# LQFP.net
KiCad netlist of a schematic drawn in Altium Designer
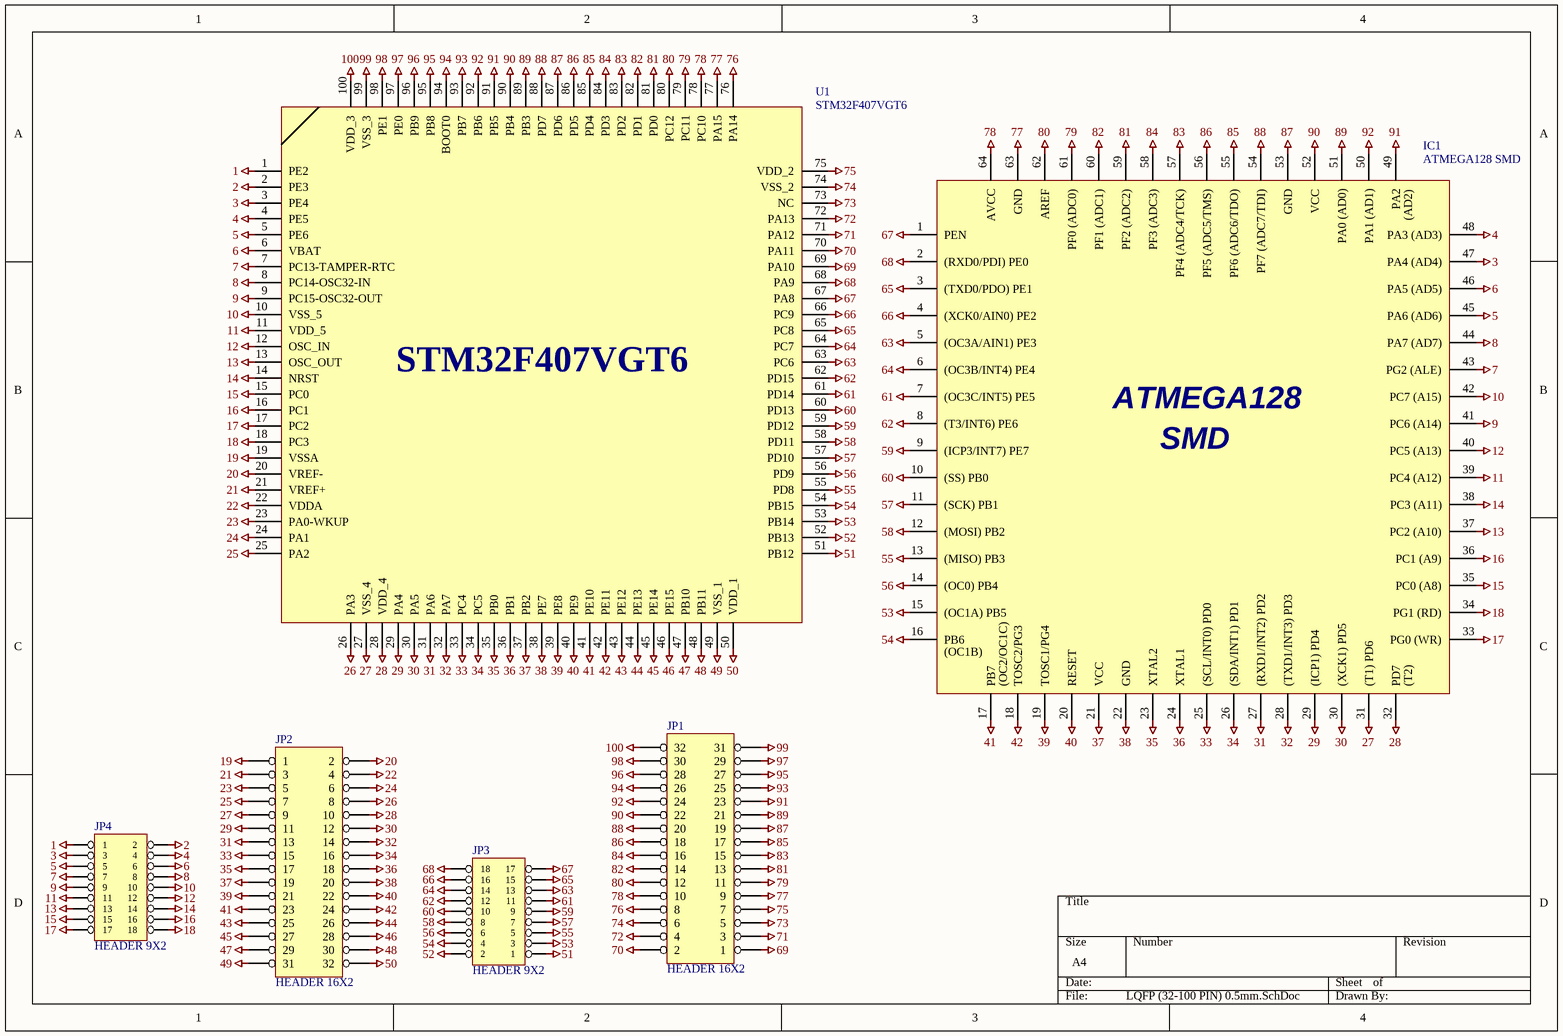
[diagram p0: LQFP (32-100 PIN) 0.5mm.SchDoc]

(export (version "E")
  (design (tool "Eeschema 10.0.6"))
  (components
    (comp (ref "IC1")
      (value "ATMEGA128 SMD")
      (footprint "TQFP 32-64 0.8mm")
      (libsource (lib "MICROCONTROLLER") (part "ATMEGA128 SMD"))
    )
    (comp (ref "JP1")
      (value "HEADER 16X2")
      (footprint "Double Row 32P 2.54mm")
      (libsource (lib "CONNECTOR") (part "HEADER 16X2"))
    )
    (comp (ref "JP2")
      (value "HEADER 16X2")
      (footprint "Double Row 32P 2.54mm")
      (libsource (lib "") (part "HEADER 16X2_1"))
    )
    (comp (ref "JP3")
      (value "HEADER 9X2")
      (footprint "Double Row 18P 2.54mm")
      (libsource (lib "CONNECTOR") (part "HEADER 9X2"))
    )
    (comp (ref "JP4")
      (value "HEADER 9X2")
      (footprint "Double Row 18P 2.54mm")
      (libsource (lib "") (part "HEADER 9X2_1"))
    )
    (comp (ref "U1")
      (value "STM32F407VGT6")
      (footprint "LQFP (32-100 PIN) 0.5mm")
      (libsource (lib "MICROCONTROLLER") (part "STM32F407VGT6"))
    )
  )
  (nets
    (net (code "1") (name "1") (class "Default")
      (node (ref "JP4") (pin "1") (pinfunction "1_1") (pintype "passive"))
      (node (ref "U1") (pin "1") (pinfunction "PE2_1") (pintype "passive"))
    )
    (net (code "2") (name "2") (class "Default")
      (node (ref "JP4") (pin "2") (pinfunction "2_2") (pintype "passive"))
      (node (ref "U1") (pin "2") (pinfunction "PE3_2") (pintype "passive"))
    )
    (net (code "3") (name "3") (class "Default")
      (node (ref "IC1") (pin "47") (pinfunction "PA4_(AD4)_47") (pintype "passive"))
      (node (ref "JP4") (pin "3") (pinfunction "3_3") (pintype "passive"))
      (node (ref "U1") (pin "3") (pinfunction "PE4_3") (pintype "passive"))
    )
    (net (code "4") (name "4") (class "Default")
      (node (ref "IC1") (pin "48") (pinfunction "PA3_(AD3)_48") (pintype "passive"))
      (node (ref "JP4") (pin "4") (pinfunction "4_4") (pintype "passive"))
      (node (ref "U1") (pin "4") (pinfunction "PE5_4") (pintype "passive"))
    )
    (net (code "5") (name "5") (class "Default")
      (node (ref "IC1") (pin "45") (pinfunction "PA6_(AD6)_45") (pintype "passive"))
      (node (ref "JP4") (pin "5") (pinfunction "5_5") (pintype "passive"))
      (node (ref "U1") (pin "5") (pinfunction "PE6_5") (pintype "passive"))
    )
    (net (code "6") (name "6") (class "Default")
      (node (ref "IC1") (pin "46") (pinfunction "PA5_(AD5)_46") (pintype "passive"))
      (node (ref "JP4") (pin "6") (pinfunction "6_6") (pintype "passive"))
      (node (ref "U1") (pin "6") (pinfunction "VBAT_6") (pintype "passive"))
    )
    (net (code "7") (name "7") (class "Default")
      (node (ref "IC1") (pin "43") (pinfunction "PG2_(ALE)_43") (pintype "passive"))
      (node (ref "JP4") (pin "7") (pinfunction "7_7") (pintype "passive"))
      (node (ref "U1") (pin "7") (pinfunction "PC13-TAMPER-RTC_7") (pintype "passive"))
    )
    (net (code "8") (name "8") (class "Default")
      (node (ref "IC1") (pin "44") (pinfunction "PA7_(AD7)_44") (pintype "passive"))
      (node (ref "JP4") (pin "8") (pinfunction "8_8") (pintype "passive"))
      (node (ref "U1") (pin "8") (pinfunction "PC14-OSC32-IN_8") (pintype "passive"))
    )
    (net (code "9") (name "9") (class "Default")
      (node (ref "IC1") (pin "41") (pinfunction "PC6_(A14)_41") (pintype "passive"))
      (node (ref "JP4") (pin "9") (pinfunction "9_9") (pintype "passive"))
      (node (ref "U1") (pin "9") (pinfunction "PC15-OSC32-OUT_9") (pintype "passive"))
    )
    (net (code "10") (name "10") (class "Default")
      (node (ref "IC1") (pin "42") (pinfunction "PC7_(A15)_42") (pintype "passive"))
      (node (ref "JP4") (pin "10") (pinfunction "10_10") (pintype "passive"))
      (node (ref "U1") (pin "10") (pinfunction "VSS_5_10") (pintype "passive"))
    )
    (net (code "11") (name "11") (class "Default")
      (node (ref "IC1") (pin "39") (pinfunction "PC4_(A12)_39") (pintype "passive"))
      (node (ref "JP4") (pin "11") (pinfunction "11_11") (pintype "passive"))
      (node (ref "U1") (pin "11") (pinfunction "VDD_5_11") (pintype "passive"))
    )
    (net (code "12") (name "12") (class "Default")
      (node (ref "IC1") (pin "40") (pinfunction "PC5_(A13)_40") (pintype "passive"))
      (node (ref "JP4") (pin "12") (pinfunction "12_12") (pintype "passive"))
      (node (ref "U1") (pin "12") (pinfunction "OSC_IN_12") (pintype "passive"))
    )
    (net (code "13") (name "13") (class "Default")
      (node (ref "IC1") (pin "37") (pinfunction "PC2_(A10)_37") (pintype "passive"))
      (node (ref "JP4") (pin "13") (pinfunction "13_13") (pintype "passive"))
      (node (ref "U1") (pin "13") (pinfunction "OSC_OUT_13") (pintype "passive"))
    )
    (net (code "14") (name "14") (class "Default")
      (node (ref "IC1") (pin "38") (pinfunction "PC3_(A11)_38") (pintype "passive"))
      (node (ref "JP4") (pin "14") (pinfunction "14_14") (pintype "passive"))
      (node (ref "U1") (pin "14") (pinfunction "NRST_14") (pintype "passive"))
    )
    (net (code "15") (name "15") (class "Default")
      (node (ref "IC1") (pin "35") (pinfunction "PC0_(A8)_35") (pintype "passive"))
      (node (ref "JP4") (pin "15") (pinfunction "15_15") (pintype "passive"))
      (node (ref "U1") (pin "15") (pinfunction "PC0_15") (pintype "passive"))
    )
    (net (code "16") (name "16") (class "Default")
      (node (ref "IC1") (pin "36") (pinfunction "PC1_(A9)_36") (pintype "passive"))
      (node (ref "JP4") (pin "16") (pinfunction "16_16") (pintype "passive"))
      (node (ref "U1") (pin "16") (pinfunction "PC1_16") (pintype "passive"))
    )
    (net (code "17") (name "17") (class "Default")
      (node (ref "IC1") (pin "33") (pinfunction "PG0_(WR)_33") (pintype "passive"))
      (node (ref "JP4") (pin "17") (pinfunction "17_17") (pintype "passive"))
      (node (ref "U1") (pin "17") (pinfunction "PC2_17") (pintype "passive"))
    )
    (net (code "18") (name "18") (class "Default")
      (node (ref "IC1") (pin "34") (pinfunction "PG1_(RD)_34") (pintype "passive"))
      (node (ref "JP4") (pin "18") (pinfunction "18_18") (pintype "passive"))
      (node (ref "U1") (pin "18") (pinfunction "PC3_18") (pintype "passive"))
    )
    (net (code "19") (name "19") (class "Default")
      (node (ref "JP2") (pin "1") (pinfunction "1_1") (pintype "passive"))
      (node (ref "U1") (pin "19") (pinfunction "VSSA_19") (pintype "passive"))
    )
    (net (code "20") (name "20") (class "Default")
      (node (ref "JP2") (pin "2") (pinfunction "2_2") (pintype "passive"))
      (node (ref "U1") (pin "20") (pinfunction "VREF-_20") (pintype "passive"))
    )
    (net (code "21") (name "21") (class "Default")
      (node (ref "JP2") (pin "3") (pinfunction "3_3") (pintype "passive"))
      (node (ref "U1") (pin "21") (pinfunction "VREF+_21") (pintype "passive"))
    )
    (net (code "22") (name "22") (class "Default")
      (node (ref "JP2") (pin "4") (pinfunction "4_4") (pintype "passive"))
      (node (ref "U1") (pin "22") (pinfunction "VDDA_22") (pintype "passive"))
    )
    (net (code "23") (name "23") (class "Default")
      (node (ref "JP2") (pin "5") (pinfunction "5_5") (pintype "passive"))
      (node (ref "U1") (pin "23") (pinfunction "PA0-WKUP_23") (pintype "passive"))
    )
    (net (code "24") (name "24") (class "Default")
      (node (ref "JP2") (pin "6") (pinfunction "6_6") (pintype "passive"))
      (node (ref "U1") (pin "24") (pinfunction "PA1_24") (pintype "passive"))
    )
    (net (code "25") (name "25") (class "Default")
      (node (ref "JP2") (pin "7") (pinfunction "7_7") (pintype "passive"))
      (node (ref "U1") (pin "25") (pinfunction "PA2_25") (pintype "passive"))
    )
    (net (code "26") (name "26") (class "Default")
      (node (ref "JP2") (pin "8") (pinfunction "8_8") (pintype "passive"))
      (node (ref "U1") (pin "26") (pinfunction "PA3_26") (pintype "passive"))
    )
    (net (code "27") (name "27") (class "Default")
      (node (ref "IC1") (pin "31") (pinfunction "(T1)_PD6_31") (pintype "passive"))
      (node (ref "JP2") (pin "9") (pinfunction "9_9") (pintype "passive"))
      (node (ref "U1") (pin "27") (pinfunction "VSS_4_27") (pintype "passive"))
    )
    (net (code "28") (name "28") (class "Default")
      (node (ref "IC1") (pin "32") (pinfunction "PD7_32") (pintype "passive"))
      (node (ref "JP2") (pin "10") (pinfunction "10_10") (pintype "passive"))
      (node (ref "U1") (pin "28") (pinfunction "VDD_4_28") (pintype "passive"))
    )
    (net (code "29") (name "29") (class "Default")
      (node (ref "IC1") (pin "29") (pinfunction "(ICP1)_PD4_29") (pintype "passive"))
      (node (ref "JP2") (pin "11") (pinfunction "11_11") (pintype "passive"))
      (node (ref "U1") (pin "29") (pinfunction "PA4_29") (pintype "passive"))
    )
    (net (code "30") (name "30") (class "Default")
      (node (ref "IC1") (pin "30") (pinfunction "(XCK1)_PD5_30") (pintype "passive"))
      (node (ref "JP2") (pin "12") (pinfunction "12_12") (pintype "passive"))
      (node (ref "U1") (pin "30") (pinfunction "PA5_30") (pintype "passive"))
    )
    (net (code "31") (name "31") (class "Default")
      (node (ref "IC1") (pin "27") (pinfunction "(RXD1/INT2)_PD2_27") (pintype "passive"))
      (node (ref "JP2") (pin "13") (pinfunction "13_13") (pintype "passive"))
      (node (ref "U1") (pin "31") (pinfunction "PA6_31") (pintype "passive"))
    )
    (net (code "32") (name "32") (class "Default")
      (node (ref "IC1") (pin "28") (pinfunction "(TXD1/INT3)_PD3_28") (pintype "passive"))
      (node (ref "JP2") (pin "14") (pinfunction "14_14") (pintype "passive"))
      (node (ref "U1") (pin "32") (pinfunction "PA7_32") (pintype "passive"))
    )
    (net (code "33") (name "33") (class "Default")
      (node (ref "IC1") (pin "25") (pinfunction "(SCL/INT0)_PD0_25") (pintype "passive"))
      (node (ref "JP2") (pin "15") (pinfunction "15_15") (pintype "passive"))
      (node (ref "U1") (pin "33") (pinfunction "PC4_33") (pintype "passive"))
    )
    (net (code "34") (name "34") (class "Default")
      (node (ref "IC1") (pin "26") (pinfunction "(SDA/INT1)_PD1_26") (pintype "passive"))
      (node (ref "JP2") (pin "16") (pinfunction "16_16") (pintype "passive"))
      (node (ref "U1") (pin "34") (pinfunction "PC5_34") (pintype "passive"))
    )
    (net (code "35") (name "35") (class "Default")
      (node (ref "IC1") (pin "23") (pinfunction "XTAL2_23") (pintype "passive"))
      (node (ref "JP2") (pin "17") (pinfunction "17_17") (pintype "passive"))
      (node (ref "U1") (pin "35") (pinfunction "PB0_35") (pintype "passive"))
    )
    (net (code "36") (name "36") (class "Default")
      (node (ref "IC1") (pin "24") (pinfunction "XTAL1_24") (pintype "passive"))
      (node (ref "JP2") (pin "18") (pinfunction "18_18") (pintype "passive"))
      (node (ref "U1") (pin "36") (pinfunction "PB1_36") (pintype "passive"))
    )
    (net (code "37") (name "37") (class "Default")
      (node (ref "IC1") (pin "21") (pinfunction "VCC_21") (pintype "passive"))
      (node (ref "JP2") (pin "19") (pinfunction "19_19") (pintype "passive"))
      (node (ref "U1") (pin "37") (pinfunction "PB2_37") (pintype "passive"))
    )
    (net (code "38") (name "38") (class "Default")
      (node (ref "IC1") (pin "22") (pinfunction "GND_22") (pintype "passive"))
      (node (ref "JP2") (pin "20") (pinfunction "20_20") (pintype "passive"))
      (node (ref "U1") (pin "38") (pinfunction "PE7_38") (pintype "passive"))
    )
    (net (code "39") (name "39") (class "Default")
      (node (ref "IC1") (pin "19") (pinfunction "TOSC1/PG4_19") (pintype "passive"))
      (node (ref "JP2") (pin "21") (pinfunction "21_21") (pintype "passive"))
      (node (ref "U1") (pin "39") (pinfunction "PE8_39") (pintype "passive"))
    )
    (net (code "40") (name "40") (class "Default")
      (node (ref "IC1") (pin "20") (pinfunction "RESET_20") (pintype "passive"))
      (node (ref "JP2") (pin "22") (pinfunction "22_22") (pintype "passive"))
      (node (ref "U1") (pin "40") (pinfunction "PE9_40") (pintype "passive"))
    )
    (net (code "41") (name "41") (class "Default")
      (node (ref "IC1") (pin "17") (pinfunction "PB7_17") (pintype "passive"))
      (node (ref "JP2") (pin "23") (pinfunction "23_23") (pintype "passive"))
      (node (ref "U1") (pin "41") (pinfunction "PE10_41") (pintype "passive"))
    )
    (net (code "42") (name "42") (class "Default")
      (node (ref "IC1") (pin "18") (pinfunction "TOSC2/PG3_18") (pintype "passive"))
      (node (ref "JP2") (pin "24") (pinfunction "24_24") (pintype "passive"))
      (node (ref "U1") (pin "42") (pinfunction "PE11_42") (pintype "passive"))
    )
    (net (code "43") (name "43") (class "Default")
      (node (ref "JP2") (pin "25") (pinfunction "25_25") (pintype "passive"))
      (node (ref "U1") (pin "43") (pinfunction "PE12_43") (pintype "passive"))
    )
    (net (code "44") (name "44") (class "Default")
      (node (ref "JP2") (pin "26") (pinfunction "26_26") (pintype "passive"))
      (node (ref "U1") (pin "44") (pinfunction "PE13_44") (pintype "passive"))
    )
    (net (code "45") (name "45") (class "Default")
      (node (ref "JP2") (pin "27") (pinfunction "27_27") (pintype "passive"))
      (node (ref "U1") (pin "45") (pinfunction "PE14_45") (pintype "passive"))
    )
    (net (code "46") (name "46") (class "Default")
      (node (ref "JP2") (pin "28") (pinfunction "28_28") (pintype "passive"))
      (node (ref "U1") (pin "46") (pinfunction "PE15_46") (pintype "passive"))
    )
    (net (code "47") (name "47") (class "Default")
      (node (ref "JP2") (pin "29") (pinfunction "29_29") (pintype "passive"))
      (node (ref "U1") (pin "47") (pinfunction "PB10_47") (pintype "passive"))
    )
    (net (code "48") (name "48") (class "Default")
      (node (ref "JP2") (pin "30") (pinfunction "30_30") (pintype "passive"))
      (node (ref "U1") (pin "48") (pinfunction "PB11_48") (pintype "passive"))
    )
    (net (code "49") (name "49") (class "Default")
      (node (ref "JP2") (pin "31") (pinfunction "31_31") (pintype "passive"))
      (node (ref "U1") (pin "49") (pinfunction "VSS_1_49") (pintype "passive"))
    )
    (net (code "50") (name "50") (class "Default")
      (node (ref "JP2") (pin "32") (pinfunction "32_32") (pintype "passive"))
      (node (ref "U1") (pin "50") (pinfunction "VDD_1_50") (pintype "passive"))
    )
    (net (code "51") (name "51") (class "Default")
      (node (ref "JP3") (pin "1") (pinfunction "1_1") (pintype "passive"))
      (node (ref "U1") (pin "51") (pinfunction "PB12_51") (pintype "passive"))
    )
    (net (code "52") (name "52") (class "Default")
      (node (ref "JP3") (pin "2") (pinfunction "2_2") (pintype "passive"))
      (node (ref "U1") (pin "52") (pinfunction "PB13_52") (pintype "passive"))
    )
    (net (code "53") (name "53") (class "Default")
      (node (ref "IC1") (pin "15") (pinfunction "(OC1A)_PB5_15") (pintype "passive"))
      (node (ref "JP3") (pin "3") (pinfunction "3_3") (pintype "passive"))
      (node (ref "U1") (pin "53") (pinfunction "PB14_53") (pintype "passive"))
    )
    (net (code "54") (name "54") (class "Default")
      (node (ref "IC1") (pin "16") (pinfunction "PB6_16") (pintype "passive"))
      (node (ref "JP3") (pin "4") (pinfunction "4_4") (pintype "passive"))
      (node (ref "U1") (pin "54") (pinfunction "PB15_54") (pintype "passive"))
    )
    (net (code "55") (name "55") (class "Default")
      (node (ref "IC1") (pin "13") (pinfunction "(MISO)_PB3_13") (pintype "passive"))
      (node (ref "JP3") (pin "5") (pinfunction "5_5") (pintype "passive"))
      (node (ref "U1") (pin "55") (pinfunction "PD8_55") (pintype "passive"))
    )
    (net (code "56") (name "56") (class "Default")
      (node (ref "IC1") (pin "14") (pinfunction "(OC0)_PB4_14") (pintype "passive"))
      (node (ref "JP3") (pin "6") (pinfunction "6_6") (pintype "passive"))
      (node (ref "U1") (pin "56") (pinfunction "PD9_56") (pintype "passive"))
    )
    (net (code "57") (name "57") (class "Default")
      (node (ref "IC1") (pin "11") (pinfunction "(SCK)_PB1_11") (pintype "passive"))
      (node (ref "JP3") (pin "7") (pinfunction "7_7") (pintype "passive"))
      (node (ref "U1") (pin "57") (pinfunction "PD10_57") (pintype "passive"))
    )
    (net (code "58") (name "58") (class "Default")
      (node (ref "IC1") (pin "12") (pinfunction "(MOSI)_PB2_12") (pintype "passive"))
      (node (ref "JP3") (pin "8") (pinfunction "8_8") (pintype "passive"))
      (node (ref "U1") (pin "58") (pinfunction "PD11_58") (pintype "passive"))
    )
    (net (code "59") (name "59") (class "Default")
      (node (ref "IC1") (pin "9") (pinfunction "(ICP3/INT7)_PE7_9") (pintype "passive"))
      (node (ref "JP3") (pin "9") (pinfunction "9_9") (pintype "passive"))
      (node (ref "U1") (pin "59") (pinfunction "PD12_59") (pintype "passive"))
    )
    (net (code "60") (name "60") (class "Default")
      (node (ref "IC1") (pin "10") (pinfunction "(SS)_PB0_10") (pintype "passive"))
      (node (ref "JP3") (pin "10") (pinfunction "10_10") (pintype "passive"))
      (node (ref "U1") (pin "60") (pinfunction "PD13_60") (pintype "passive"))
    )
    (net (code "61") (name "61") (class "Default")
      (node (ref "IC1") (pin "7") (pinfunction "(OC3C/INT5)_PE5_7") (pintype "passive"))
      (node (ref "JP3") (pin "11") (pinfunction "11_11") (pintype "passive"))
      (node (ref "U1") (pin "61") (pinfunction "PD14_61") (pintype "passive"))
    )
    (net (code "62") (name "62") (class "Default")
      (node (ref "IC1") (pin "8") (pinfunction "(T3/INT6)_PE6_8") (pintype "passive"))
      (node (ref "JP3") (pin "12") (pinfunction "12_12") (pintype "passive"))
      (node (ref "U1") (pin "62") (pinfunction "PD15_62") (pintype "passive"))
    )
    (net (code "63") (name "63") (class "Default")
      (node (ref "IC1") (pin "5") (pinfunction "(OC3A/AIN1)_PE3_5") (pintype "passive"))
      (node (ref "JP3") (pin "13") (pinfunction "13_13") (pintype "passive"))
      (node (ref "U1") (pin "63") (pinfunction "PC6_63") (pintype "passive"))
    )
    (net (code "64") (name "64") (class "Default")
      (node (ref "IC1") (pin "6") (pinfunction "(OC3B/INT4)_PE4_6") (pintype "passive"))
      (node (ref "JP3") (pin "14") (pinfunction "14_14") (pintype "passive"))
      (node (ref "U1") (pin "64") (pinfunction "PC7_64") (pintype "passive"))
    )
    (net (code "65") (name "65") (class "Default")
      (node (ref "IC1") (pin "3") (pinfunction "(TXD0/PDO)_PE1_3") (pintype "passive"))
      (node (ref "JP3") (pin "15") (pinfunction "15_15") (pintype "passive"))
      (node (ref "U1") (pin "65") (pinfunction "PC8_65") (pintype "passive"))
    )
    (net (code "66") (name "66") (class "Default")
      (node (ref "IC1") (pin "4") (pinfunction "(XCK0/AIN0)_PE2_4") (pintype "passive"))
      (node (ref "JP3") (pin "16") (pinfunction "16_16") (pintype "passive"))
      (node (ref "U1") (pin "66") (pinfunction "PC9_66") (pintype "passive"))
    )
    (net (code "67") (name "67") (class "Default")
      (node (ref "IC1") (pin "1") (pinfunction "PEN_1") (pintype "passive"))
      (node (ref "JP3") (pin "17") (pinfunction "17_17") (pintype "passive"))
      (node (ref "U1") (pin "67") (pinfunction "PA8_67") (pintype "passive"))
    )
    (net (code "68") (name "68") (class "Default")
      (node (ref "IC1") (pin "2") (pinfunction "(RXD0/PDI)_PE0_2") (pintype "passive"))
      (node (ref "JP3") (pin "18") (pinfunction "18_18") (pintype "passive"))
      (node (ref "U1") (pin "68") (pinfunction "PA9_68") (pintype "passive"))
    )
    (net (code "69") (name "69") (class "Default")
      (node (ref "JP1") (pin "1") (pinfunction "1_1") (pintype "passive"))
      (node (ref "U1") (pin "69") (pinfunction "PA10_69") (pintype "passive"))
    )
    (net (code "70") (name "70") (class "Default")
      (node (ref "JP1") (pin "2") (pinfunction "2_2") (pintype "passive"))
      (node (ref "U1") (pin "70") (pinfunction "PA11_70") (pintype "passive"))
    )
    (net (code "71") (name "71") (class "Default")
      (node (ref "JP1") (pin "3") (pinfunction "3_3") (pintype "passive"))
      (node (ref "U1") (pin "71") (pinfunction "PA12_71") (pintype "passive"))
    )
    (net (code "72") (name "72") (class "Default")
      (node (ref "JP1") (pin "4") (pinfunction "4_4") (pintype "passive"))
      (node (ref "U1") (pin "72") (pinfunction "PA13_72") (pintype "passive"))
    )
    (net (code "73") (name "73") (class "Default")
      (node (ref "JP1") (pin "5") (pinfunction "5_5") (pintype "passive"))
      (node (ref "U1") (pin "73") (pinfunction "NC_73") (pintype "passive"))
    )
    (net (code "74") (name "74") (class "Default")
      (node (ref "JP1") (pin "6") (pinfunction "6_6") (pintype "passive"))
      (node (ref "U1") (pin "74") (pinfunction "VSS_2_74") (pintype "passive"))
    )
    (net (code "75") (name "75") (class "Default")
      (node (ref "JP1") (pin "7") (pinfunction "7_7") (pintype "passive"))
      (node (ref "U1") (pin "75") (pinfunction "VDD_2_75") (pintype "passive"))
    )
    (net (code "76") (name "76") (class "Default")
      (node (ref "JP1") (pin "8") (pinfunction "8_8") (pintype "passive"))
      (node (ref "U1") (pin "76") (pinfunction "PA14_76") (pintype "passive"))
    )
    (net (code "77") (name "77") (class "Default")
      (node (ref "IC1") (pin "63") (pinfunction "GND_63") (pintype "passive"))
      (node (ref "JP1") (pin "9") (pinfunction "9_9") (pintype "passive"))
      (node (ref "U1") (pin "77") (pinfunction "PA15_77") (pintype "passive"))
    )
    (net (code "78") (name "78") (class "Default")
      (node (ref "IC1") (pin "64") (pinfunction "AVCC_64") (pintype "passive"))
      (node (ref "JP1") (pin "10") (pinfunction "10_10") (pintype "passive"))
      (node (ref "U1") (pin "78") (pinfunction "PC10_78") (pintype "passive"))
    )
    (net (code "79") (name "79") (class "Default")
      (node (ref "IC1") (pin "61") (pinfunction "PF0_(ADC0)_61") (pintype "passive"))
      (node (ref "JP1") (pin "11") (pinfunction "11_11") (pintype "passive"))
      (node (ref "U1") (pin "79") (pinfunction "PC11_79") (pintype "passive"))
    )
    (net (code "80") (name "80") (class "Default")
      (node (ref "IC1") (pin "62") (pinfunction "AREF_62") (pintype "passive"))
      (node (ref "JP1") (pin "12") (pinfunction "12_12") (pintype "passive"))
      (node (ref "U1") (pin "80") (pinfunction "PC12_80") (pintype "passive"))
    )
    (net (code "81") (name "81") (class "Default")
      (node (ref "IC1") (pin "59") (pinfunction "PF2_(ADC2)_59") (pintype "passive"))
      (node (ref "JP1") (pin "13") (pinfunction "13_13") (pintype "passive"))
      (node (ref "U1") (pin "81") (pinfunction "PD0_81") (pintype "passive"))
    )
    (net (code "82") (name "82") (class "Default")
      (node (ref "IC1") (pin "60") (pinfunction "PF1_(ADC1)_60") (pintype "passive"))
      (node (ref "JP1") (pin "14") (pinfunction "14_14") (pintype "passive"))
      (node (ref "U1") (pin "82") (pinfunction "PD1_82") (pintype "passive"))
    )
    (net (code "83") (name "83") (class "Default")
      (node (ref "IC1") (pin "57") (pinfunction "PF4_(ADC4/TCK)_57") (pintype "passive"))
      (node (ref "JP1") (pin "15") (pinfunction "15_15") (pintype "passive"))
      (node (ref "U1") (pin "83") (pinfunction "PD2_83") (pintype "passive"))
    )
    (net (code "84") (name "84") (class "Default")
      (node (ref "IC1") (pin "58") (pinfunction "PF3_(ADC3)_58") (pintype "passive"))
      (node (ref "JP1") (pin "16") (pinfunction "16_16") (pintype "passive"))
      (node (ref "U1") (pin "84") (pinfunction "PD3_84") (pintype "passive"))
    )
    (net (code "85") (name "85") (class "Default")
      (node (ref "IC1") (pin "55") (pinfunction "PF6_(ADC6/TDO)_55") (pintype "passive"))
      (node (ref "JP1") (pin "17") (pinfunction "17_17") (pintype "passive"))
      (node (ref "U1") (pin "85") (pinfunction "PD4_85") (pintype "passive"))
    )
    (net (code "86") (name "86") (class "Default")
      (node (ref "IC1") (pin "56") (pinfunction "PF5_(ADC5/TMS)_56") (pintype "passive"))
      (node (ref "JP1") (pin "18") (pinfunction "18_18") (pintype "passive"))
      (node (ref "U1") (pin "86") (pinfunction "PD5_86") (pintype "passive"))
    )
    (net (code "87") (name "87") (class "Default")
      (node (ref "IC1") (pin "53") (pinfunction "GND_53") (pintype "passive"))
      (node (ref "JP1") (pin "19") (pinfunction "19_19") (pintype "passive"))
      (node (ref "U1") (pin "87") (pinfunction "PD6_87") (pintype "passive"))
    )
    (net (code "88") (name "88") (class "Default")
      (node (ref "IC1") (pin "54") (pinfunction "PF7_(ADC7/TDI)_54") (pintype "passive"))
      (node (ref "JP1") (pin "20") (pinfunction "20_20") (pintype "passive"))
      (node (ref "U1") (pin "88") (pinfunction "PD7_88") (pintype "passive"))
    )
    (net (code "89") (name "89") (class "Default")
      (node (ref "IC1") (pin "51") (pinfunction "PA0_(AD0)_51") (pintype "passive"))
      (node (ref "JP1") (pin "21") (pinfunction "21_21") (pintype "passive"))
      (node (ref "U1") (pin "89") (pinfunction "PB3_89") (pintype "passive"))
    )
    (net (code "90") (name "90") (class "Default")
      (node (ref "IC1") (pin "52") (pinfunction "VCC_52") (pintype "passive"))
      (node (ref "JP1") (pin "22") (pinfunction "22_22") (pintype "passive"))
      (node (ref "U1") (pin "90") (pinfunction "PB4_90") (pintype "passive"))
    )
    (net (code "91") (name "91") (class "Default")
      (node (ref "IC1") (pin "49") (pinfunction "PA2_49") (pintype "passive"))
      (node (ref "JP1") (pin "23") (pinfunction "23_23") (pintype "passive"))
      (node (ref "U1") (pin "91") (pinfunction "PB5_91") (pintype "passive"))
    )
    (net (code "92") (name "92") (class "Default")
      (node (ref "IC1") (pin "50") (pinfunction "PA1_(AD1)_50") (pintype "passive"))
      (node (ref "JP1") (pin "24") (pinfunction "24_24") (pintype "passive"))
      (node (ref "U1") (pin "92") (pinfunction "PB6_92") (pintype "passive"))
    )
    (net (code "93") (name "93") (class "Default")
      (node (ref "JP1") (pin "25") (pinfunction "25_25") (pintype "passive"))
      (node (ref "U1") (pin "93") (pinfunction "PB7_93") (pintype "passive"))
    )
    (net (code "94") (name "94") (class "Default")
      (node (ref "JP1") (pin "26") (pinfunction "26_26") (pintype "passive"))
      (node (ref "U1") (pin "94") (pinfunction "BOOT0_94") (pintype "passive"))
    )
    (net (code "95") (name "95") (class "Default")
      (node (ref "JP1") (pin "27") (pinfunction "27_27") (pintype "passive"))
      (node (ref "U1") (pin "95") (pinfunction "PB8_95") (pintype "passive"))
    )
    (net (code "96") (name "96") (class "Default")
      (node (ref "JP1") (pin "28") (pinfunction "28_28") (pintype "passive"))
      (node (ref "U1") (pin "96") (pinfunction "PB9_96") (pintype "passive"))
    )
    (net (code "97") (name "97") (class "Default")
      (node (ref "JP1") (pin "29") (pinfunction "29_29") (pintype "passive"))
      (node (ref "U1") (pin "97") (pinfunction "PE0_97") (pintype "passive"))
    )
    (net (code "98") (name "98") (class "Default")
      (node (ref "JP1") (pin "30") (pinfunction "30_30") (pintype "passive"))
      (node (ref "U1") (pin "98") (pinfunction "PE1_98") (pintype "passive"))
    )
    (net (code "99") (name "99") (class "Default")
      (node (ref "JP1") (pin "31") (pinfunction "31_31") (pintype "passive"))
      (node (ref "U1") (pin "99") (pinfunction "VSS_3_99") (pintype "passive"))
    )
    (net (code "100") (name "100") (class "Default")
      (node (ref "JP1") (pin "32") (pinfunction "32_32") (pintype "passive"))
      (node (ref "U1") (pin "100") (pinfunction "VDD_3_100") (pintype "passive"))
    )
  )
)
